# WiFi_module.net
KiCad netlist of a schematic drawn in EAGLE
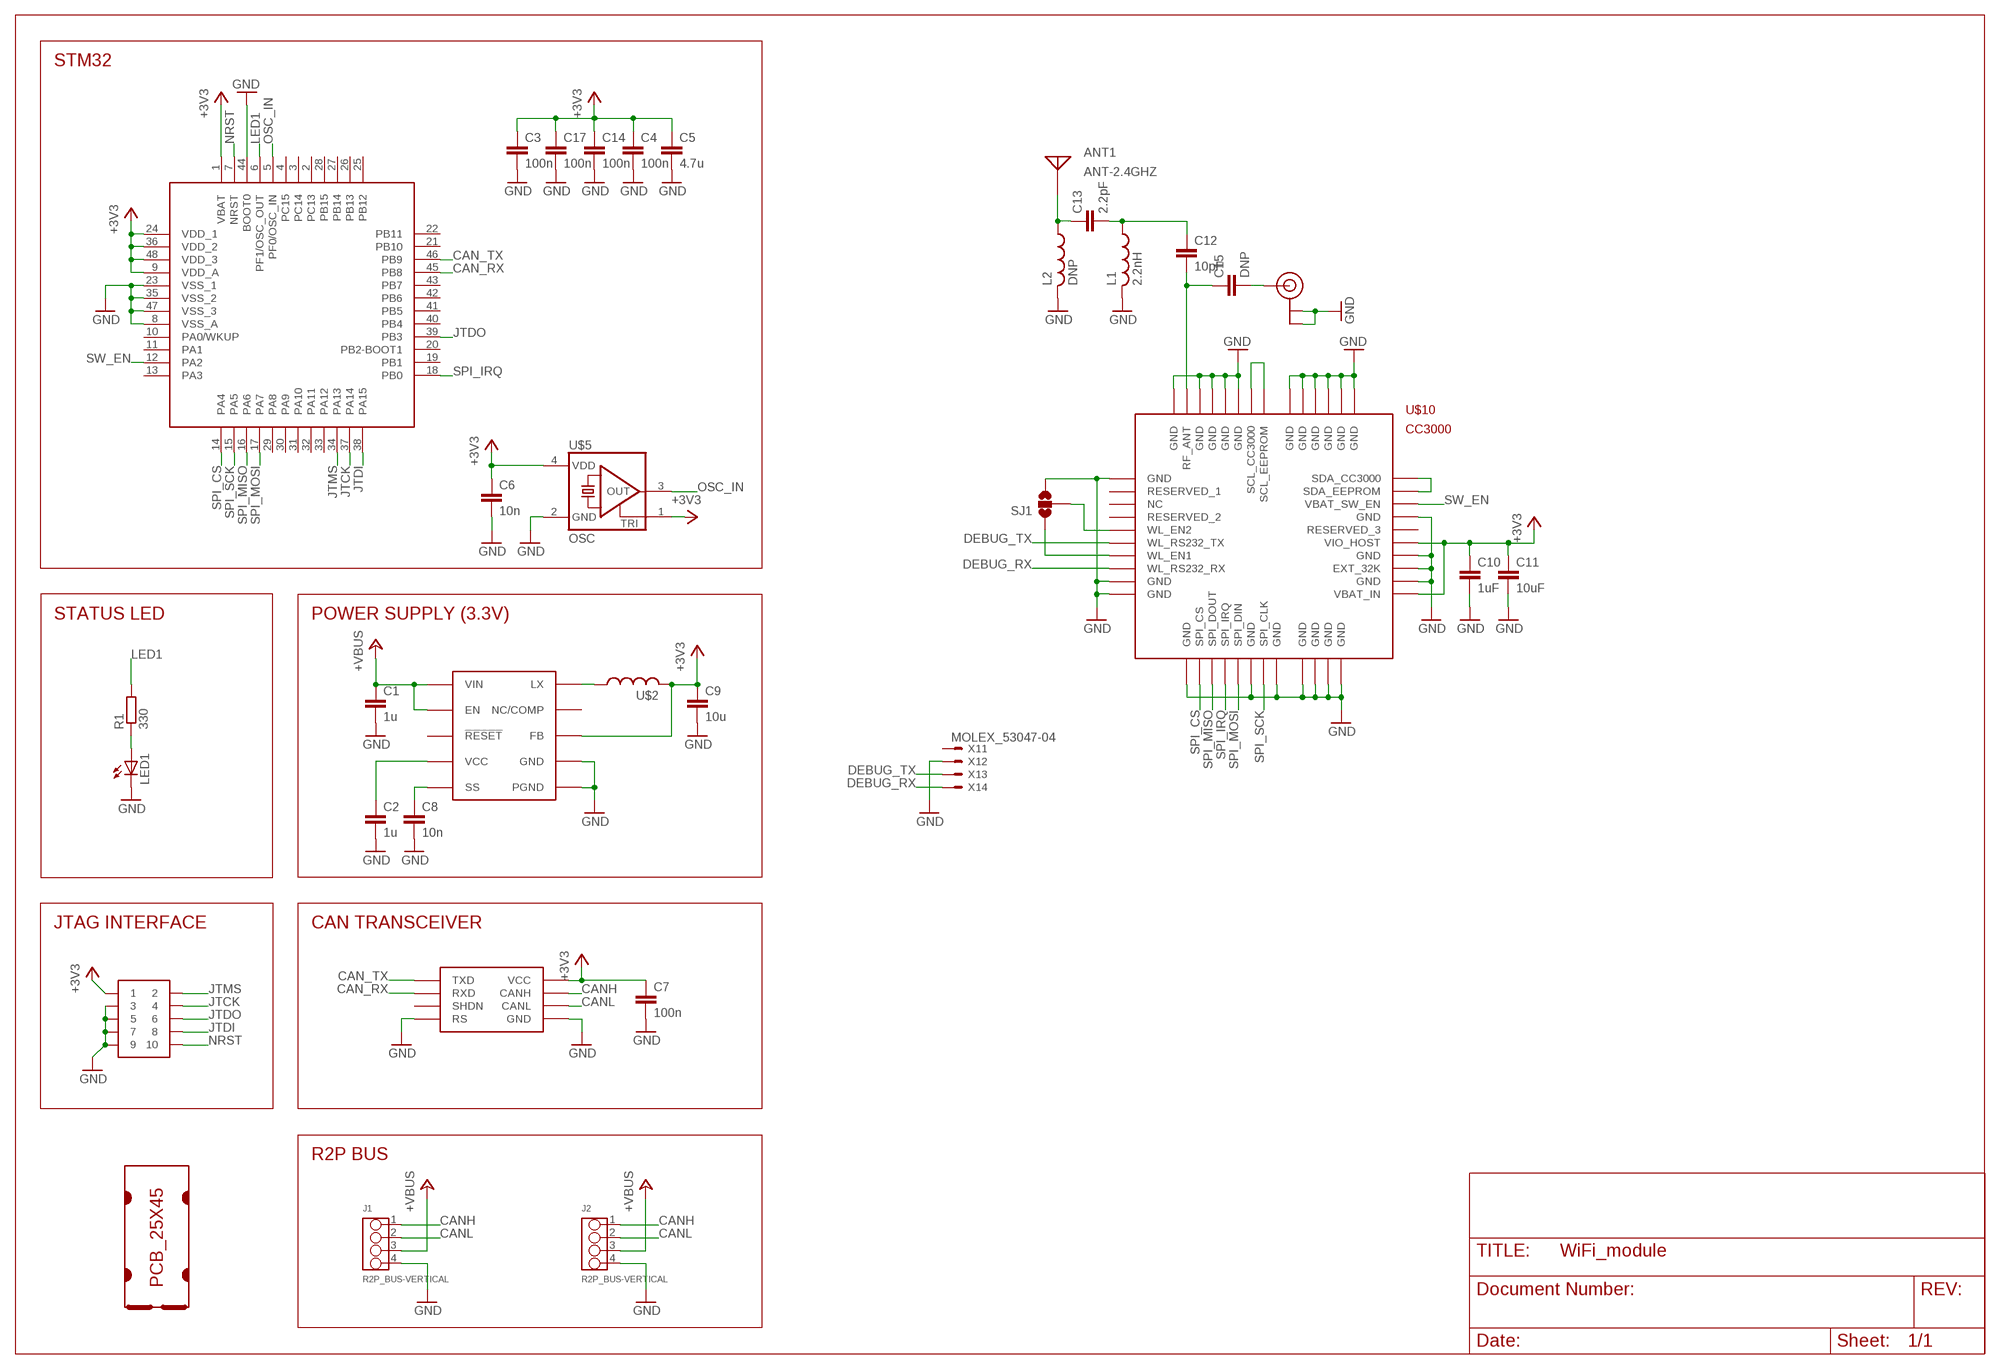
[diagram p0: schematic, sheet 1]

(export (version "E")
  (design (tool "Eeschema 10.0.6"))
  (components
    (comp (ref "ANT1")
      (value "ANT-2.4GHZ")
      (footprint "eagle-import:CHIP_ANTENNA_8X1")
      (libsource (lib "eagle-import") (part "ANT-2.4GHZ"))
    )
    (comp (ref "C1")
      (value "1u")
      (footprint "eagle-import:C1206")
      (libsource (lib "eagle-import") (part "C1206"))
    )
    (comp (ref "C2")
      (value "1u")
      (footprint "eagle-import:C0603")
      (libsource (lib "eagle-import") (part "C0603"))
    )
    (comp (ref "C3")
      (value "100n")
      (footprint "eagle-import:C0603")
      (libsource (lib "eagle-import") (part "C0603"))
    )
    (comp (ref "C4")
      (value "100n")
      (footprint "eagle-import:C0603")
      (libsource (lib "eagle-import") (part "C0603"))
    )
    (comp (ref "C5")
      (value "4.7u")
      (footprint "eagle-import:C0805")
      (libsource (lib "eagle-import") (part "C0805"))
    )
    (comp (ref "C6")
      (value "10n")
      (footprint "eagle-import:C0603")
      (libsource (lib "eagle-import") (part "C0603"))
    )
    (comp (ref "C7")
      (value "100n")
      (footprint "eagle-import:C0603")
      (libsource (lib "eagle-import") (part "C0603"))
    )
    (comp (ref "C8")
      (value "10n")
      (footprint "eagle-import:C0603")
      (libsource (lib "eagle-import") (part "C0603"))
    )
    (comp (ref "C9")
      (value "10u")
      (footprint "eagle-import:C0805")
      (libsource (lib "eagle-import") (part "C0805"))
    )
    (comp (ref "C10")
      (value "1uF")
      (footprint "eagle-import:C0603")
      (libsource (lib "eagle-import") (part "C0603"))
    )
    (comp (ref "C11")
      (value "10uF")
      (footprint "eagle-import:C0805")
      (libsource (lib "eagle-import") (part "C0805"))
    )
    (comp (ref "C12")
      (value "10pF")
      (footprint "eagle-import:C0402")
      (libsource (lib "eagle-import") (part "C0402"))
    )
    (comp (ref "C13")
      (value "2.2pF")
      (footprint "eagle-import:C0402")
      (libsource (lib "eagle-import") (part "C0402"))
    )
    (comp (ref "C14")
      (value "100n")
      (footprint "eagle-import:C0603")
      (libsource (lib "eagle-import") (part "C0603"))
    )
    (comp (ref "C15")
      (value "DNP")
      (footprint "eagle-import:C0402")
      (libsource (lib "eagle-import") (part "C0402"))
    )
    (comp (ref "C17")
      (value "100n")
      (footprint "eagle-import:C0603")
      (libsource (lib "eagle-import") (part "C0603"))
    )
    (comp (ref "J1")
      (value "R2P_BUS-VERTICAL")
      (footprint "eagle-import:OPL-EAGLE-LIBRARY_4P-2.0")
      (libsource (lib "eagle-import") (part "R2P_BUS-VERTICAL"))
    )
    (comp (ref "J2")
      (value "R2P_BUS-VERTICAL")
      (footprint "eagle-import:OPL-EAGLE-LIBRARY_4P-2.0")
      (libsource (lib "eagle-import") (part "R2P_BUS-VERTICAL"))
    )
    (comp (ref "L1")
      (value "2.2nH")
      (footprint "eagle-import:L0402")
      (libsource (lib "eagle-import") (part "L0402"))
    )
    (comp (ref "L2")
      (value "DNP")
      (footprint "eagle-import:L0402")
      (libsource (lib "eagle-import") (part "L0402"))
    )
    (comp (ref "LED1")
      (value "LED0805")
      (footprint "eagle-import:CHIPLED_0805")
      (libsource (lib "eagle-import") (part "LED0805"))
    )
    (comp (ref "R1")
      (value "330")
      (footprint "eagle-import:R0603")
      (libsource (lib "eagle-import") (part "R0603"))
    )
    (comp (ref "SJ1")
      (value "SOLDERJUMPER_2WAYPASTE1&2")
      (footprint "eagle-import:SJ_3_PASTE1&2")
      (libsource (lib "eagle-import") (part "SOLDERJUMPER_2WAYPASTE1&2"))
    )
    (comp (ref "SOT1")
      (value "MAX3051EKA")
      (footprint "eagle-import:SOT23-8L")
      (libsource (lib "eagle-import") (part "MAX3051EKA"))
    )
    (comp (ref "U$1")
      (value "PCB_25X45")
      (footprint "eagle-import:25X45")
      (libsource (lib "eagle-import") (part "PCB_25X45"))
    )
    (comp (ref "U$2")
      (value "LPS4018")
      (footprint "eagle-import:COILCRAFT_LPS4018")
      (libsource (lib "eagle-import") (part "LPS4018"))
    )
    (comp (ref "U$3")
      (value "MAX17501")
      (footprint "eagle-import:TDFN-10")
      (libsource (lib "eagle-import") (part "MAX17501"))
    )
    (comp (ref "U$4")
      (value "JTAG-TH")
      (footprint "eagle-import:SAMTEC_FTSH-105-TH")
      (libsource (lib "eagle-import") (part "JTAG-TH"))
    )
    (comp (ref "U$5")
      (value "OSC")
      (footprint "eagle-import:XTAL_2.5X2")
      (libsource (lib "eagle-import") (part "OSC"))
    )
    (comp (ref "U$6")
      (value "STM32F303CTX")
      (footprint "eagle-import:LQFP48")
      (libsource (lib "eagle-import") (part "STM32F303CTX"))
    )
    (comp (ref "U$10")
      (value "CC3000")
      (footprint "eagle-import:CC3000")
      (libsource (lib "eagle-import") (part "CC3000"))
    )
    (comp (ref "U$11")
      (value "U.FL")
      (footprint "eagle-import:U.FL")
      (libsource (lib "eagle-import") (part "U.FL"))
    )
    (comp (ref "X1")
      (value "MOLEX_53047-04")
      (footprint "eagle-import:MOLEX_53047-04")
      (fields (field (name "MF") "WALDOM/MOLEX") (field (name "MPN") "53047-0410"))
      (libsource (lib "eagle-import") (part "MOLEX_53?-04047"))
    )
  )
  (nets
    (net (code "1") (name "+3V3") (class "Default")
      (node (ref "C10") (pin "1") (pinfunction "1_1") (pintype "passive"))
      (node (ref "C11") (pin "1") (pinfunction "1_1") (pintype "passive"))
      (node (ref "C14") (pin "1") (pinfunction "1_1") (pintype "passive"))
      (node (ref "C17") (pin "1") (pinfunction "1_1") (pintype "passive"))
      (node (ref "C3") (pin "1") (pinfunction "1_1") (pintype "passive"))
      (node (ref "C4") (pin "1") (pinfunction "1_1") (pintype "passive"))
      (node (ref "C5") (pin "1") (pinfunction "1_1") (pintype "passive"))
      (node (ref "C6") (pin "1") (pinfunction "1_1") (pintype "passive"))
      (node (ref "C7") (pin "1") (pinfunction "1_1") (pintype "passive"))
      (node (ref "C9") (pin "1") (pinfunction "1_1") (pintype "passive"))
      (node (ref "SOT1") (pin "3") (pinfunction "VCC_3") (pintype "bidirectional"))
      (node (ref "U$10") (pin "P$19") (pinfunction "VBAT_IN_P$19") (pintype "bidirectional"))
      (node (ref "U$10") (pin "P$23") (pinfunction "VIO_HOST_P$23") (pintype "bidirectional"))
      (node (ref "U$2") (pin "P$2") (pinfunction "2_P$2") (pintype "passive"))
      (node (ref "U$3") (pin "P$5") (pinfunction "FB_P$5") (pintype "bidirectional"))
      (node (ref "U$4") (pin "1") (pinfunction "1_1") (pintype "bidirectional"))
      (node (ref "U$5") (pin "1") (pinfunction "TRI_1") (pintype "input"))
      (node (ref "U$5") (pin "4") (pinfunction "VDD_4") (pintype "power_in"))
      (node (ref "U$6") (pin "1") (pinfunction "VBAT_1") (pintype "bidirectional"))
      (node (ref "U$6") (pin "24") (pinfunction "VDD_1_24") (pintype "bidirectional"))
      (node (ref "U$6") (pin "36") (pinfunction "VDD_2_36") (pintype "bidirectional"))
      (node (ref "U$6") (pin "48") (pinfunction "VDD_3_48") (pintype "bidirectional"))
      (node (ref "U$6") (pin "9") (pinfunction "VDD_A_9") (pintype "bidirectional"))
    )
    (net (code "2") (name "+VBUS") (class "Default")
      (node (ref "C1") (pin "1") (pinfunction "1_1") (pintype "passive"))
      (node (ref "J1") (pin "3") (pinfunction "3_3") (pintype "bidirectional"))
      (node (ref "J2") (pin "3") (pinfunction "3_3") (pintype "bidirectional"))
      (node (ref "U$3") (pin "P$2") (pinfunction "VIN_P$2") (pintype "bidirectional"))
      (node (ref "U$3") (pin "P$3") (pinfunction "EN_P$3") (pintype "bidirectional"))
    )
    (net (code "3") (name "/CANH") (class "Default")
      (node (ref "J1") (pin "1") (pinfunction "1_1") (pintype "bidirectional"))
      (node (ref "J2") (pin "1") (pinfunction "1_1") (pintype "bidirectional"))
      (node (ref "SOT1") (pin "7") (pinfunction "CANH_7") (pintype "bidirectional"))
    )
    (net (code "4") (name "/CANL") (class "Default")
      (node (ref "J1") (pin "2") (pinfunction "2_2") (pintype "bidirectional"))
      (node (ref "J2") (pin "2") (pinfunction "2_2") (pintype "bidirectional"))
      (node (ref "SOT1") (pin "6") (pinfunction "CANL_6") (pintype "bidirectional"))
    )
    (net (code "5") (name "/CAN_RX") (class "Default")
      (node (ref "SOT1") (pin "4") (pinfunction "RXD_4") (pintype "bidirectional"))
      (node (ref "U$6") (pin "45") (pinfunction "PB8_45") (pintype "bidirectional"))
    )
    (net (code "6") (name "/CAN_TX") (class "Default")
      (node (ref "SOT1") (pin "1") (pinfunction "TXD_1") (pintype "bidirectional"))
      (node (ref "U$6") (pin "46") (pinfunction "PB9_46") (pintype "bidirectional"))
    )
    (net (code "7") (name "/DEBUG_RX") (class "Default")
      (node (ref "U$10") (pin "P$8") (pinfunction "WL_RS232_RX_P$8") (pintype "bidirectional"))
      (node (ref "X1") (pin "4") (pinfunction "S_4") (pintype "passive"))
    )
    (net (code "8") (name "/DEBUG_TX") (class "Default")
      (node (ref "U$10") (pin "P$6") (pinfunction "WL_RS232_TX_P$6") (pintype "bidirectional"))
      (node (ref "X1") (pin "3") (pinfunction "S_3") (pintype "passive"))
    )
    (net (code "9") (name "/JTCK") (class "Default")
      (node (ref "U$4") (pin "4") (pinfunction "4_4") (pintype "bidirectional"))
      (node (ref "U$6") (pin "37") (pinfunction "PA14_37") (pintype "bidirectional"))
    )
    (net (code "10") (name "/JTDI") (class "Default")
      (node (ref "U$4") (pin "8") (pinfunction "8_8") (pintype "bidirectional"))
      (node (ref "U$6") (pin "38") (pinfunction "PA15_38") (pintype "bidirectional"))
    )
    (net (code "11") (name "/JTDO") (class "Default")
      (node (ref "U$4") (pin "6") (pinfunction "6_6") (pintype "bidirectional"))
      (node (ref "U$6") (pin "39") (pinfunction "PB3_39") (pintype "bidirectional"))
    )
    (net (code "12") (name "/JTMS") (class "Default")
      (node (ref "U$4") (pin "2") (pinfunction "2_2") (pintype "bidirectional"))
      (node (ref "U$6") (pin "34") (pinfunction "PA13_34") (pintype "bidirectional"))
    )
    (net (code "13") (name "/LED1") (class "Default")
      (node (ref "R1") (pin "2") (pinfunction "2_2") (pintype "passive"))
      (node (ref "U$6") (pin "6") (pinfunction "PF1/OSC_OUT_6") (pintype "bidirectional"))
    )
    (net (code "14") (name "/NRST") (class "Default")
      (node (ref "U$4") (pin "10") (pinfunction "10_10") (pintype "bidirectional"))
      (node (ref "U$6") (pin "7") (pinfunction "NRST_7") (pintype "bidirectional"))
    )
    (net (code "15") (name "/OSC_IN") (class "Default")
      (node (ref "U$5") (pin "3") (pinfunction "OUT_3") (pintype "output"))
      (node (ref "U$6") (pin "5") (pinfunction "PF0/OSC_IN_5") (pintype "bidirectional"))
    )
    (net (code "16") (name "/SPI_CS") (class "Default")
      (node (ref "U$10") (pin "P$12") (pinfunction "SPI_CS_P$12") (pintype "bidirectional"))
      (node (ref "U$6") (pin "14") (pinfunction "PA4_14") (pintype "bidirectional"))
    )
    (net (code "17") (name "/SPI_IRQ") (class "Default")
      (node (ref "U$10") (pin "P$14") (pinfunction "SPI_IRQ_P$14") (pintype "bidirectional"))
      (node (ref "U$6") (pin "18") (pinfunction "PB0_18") (pintype "bidirectional"))
    )
    (net (code "18") (name "/SPI_MISO") (class "Default")
      (node (ref "U$10") (pin "P$13") (pinfunction "SPI_DOUT_P$13") (pintype "bidirectional"))
      (node (ref "U$6") (pin "16") (pinfunction "PA6_16") (pintype "bidirectional"))
    )
    (net (code "19") (name "/SPI_MOSI") (class "Default")
      (node (ref "U$10") (pin "P$15") (pinfunction "SPI_DIN_P$15") (pintype "bidirectional"))
      (node (ref "U$6") (pin "17") (pinfunction "PA7_17") (pintype "bidirectional"))
    )
    (net (code "20") (name "/SPI_SCK") (class "Default")
      (node (ref "U$10") (pin "P$17") (pinfunction "SPI_CLK_P$17") (pintype "bidirectional"))
      (node (ref "U$6") (pin "15") (pinfunction "PA5_15") (pintype "bidirectional"))
    )
    (net (code "21") (name "/SW_EN") (class "Default")
      (node (ref "U$10") (pin "P$26") (pinfunction "VBAT_SW_EN_P$26") (pintype "bidirectional"))
      (node (ref "U$6") (pin "12") (pinfunction "PA2_12") (pintype "bidirectional"))
    )
    (net (code "22") (name "GND") (class "Default")
      (node (ref "C1") (pin "2") (pinfunction "2_2") (pintype "passive"))
      (node (ref "C10") (pin "2") (pinfunction "2_2") (pintype "passive"))
      (node (ref "C11") (pin "2") (pinfunction "2_2") (pintype "passive"))
      (node (ref "C14") (pin "2") (pinfunction "2_2") (pintype "passive"))
      (node (ref "C17") (pin "2") (pinfunction "2_2") (pintype "passive"))
      (node (ref "C2") (pin "2") (pinfunction "2_2") (pintype "passive"))
      (node (ref "C3") (pin "2") (pinfunction "2_2") (pintype "passive"))
      (node (ref "C4") (pin "2") (pinfunction "2_2") (pintype "passive"))
      (node (ref "C5") (pin "2") (pinfunction "2_2") (pintype "passive"))
      (node (ref "C6") (pin "2") (pinfunction "2_2") (pintype "passive"))
      (node (ref "C7") (pin "2") (pinfunction "2_2") (pintype "passive"))
      (node (ref "C8") (pin "2") (pinfunction "2_2") (pintype "passive"))
      (node (ref "C9") (pin "2") (pinfunction "2_2") (pintype "passive"))
      (node (ref "J1") (pin "4") (pinfunction "4_4") (pintype "bidirectional"))
      (node (ref "J2") (pin "4") (pinfunction "4_4") (pintype "bidirectional"))
      (node (ref "L1") (pin "2") (pinfunction "2_2") (pintype "passive"))
      (node (ref "L2") (pin "2") (pinfunction "2_2") (pintype "passive"))
      (node (ref "LED1") (pin "C") (pinfunction "C_C") (pintype "passive"))
      (node (ref "SJ1") (pin "3") (pinfunction "3_3") (pintype "passive"))
      (node (ref "SOT1") (pin "2") (pinfunction "GND_2") (pintype "bidirectional"))
      (node (ref "SOT1") (pin "8") (pinfunction "RS_8") (pintype "bidirectional"))
      (node (ref "U$10") (pin "P$1") (pinfunction "GND_P$1") (pintype "bidirectional"))
      (node (ref "U$10") (pin "P$10") (pinfunction "GND_P$10") (pintype "bidirectional"))
      (node (ref "U$10") (pin "P$11") (pinfunction "GND_P$11") (pintype "bidirectional"))
      (node (ref "U$10") (pin "P$16") (pinfunction "GND_P$16") (pintype "bidirectional"))
      (node (ref "U$10") (pin "P$18") (pinfunction "GND_P$18") (pintype "bidirectional"))
      (node (ref "U$10") (pin "P$20") (pinfunction "GND_P$20") (pintype "bidirectional"))
      (node (ref "U$10") (pin "P$21") (pinfunction "EXT_32K_P$21") (pintype "bidirectional"))
      (node (ref "U$10") (pin "P$22") (pinfunction "GND_P$22") (pintype "bidirectional"))
      (node (ref "U$10") (pin "P$25") (pinfunction "GND_P$25") (pintype "bidirectional"))
      (node (ref "U$10") (pin "P$31") (pinfunction "GND_P$31") (pintype "bidirectional"))
      (node (ref "U$10") (pin "P$32") (pinfunction "GND_P$32") (pintype "bidirectional"))
      (node (ref "U$10") (pin "P$33") (pinfunction "GND_P$33") (pintype "bidirectional"))
      (node (ref "U$10") (pin "P$34") (pinfunction "GND_P$34") (pintype "bidirectional"))
      (node (ref "U$10") (pin "P$36") (pinfunction "GND_P$36") (pintype "bidirectional"))
      (node (ref "U$10") (pin "P$37") (pinfunction "GND_P$37") (pintype "bidirectional"))
      (node (ref "U$10") (pin "P$38") (pinfunction "GND_P$38") (pintype "bidirectional"))
      (node (ref "U$10") (pin "P$39") (pinfunction "GND_P$39") (pintype "bidirectional"))
      (node (ref "U$10") (pin "P$40") (pinfunction "GND_P$40") (pintype "bidirectional"))
      (node (ref "U$10") (pin "P$41") (pinfunction "GND_P$41") (pintype "bidirectional"))
      (node (ref "U$10") (pin "P$42") (pinfunction "GND_P$42") (pintype "bidirectional"))
      (node (ref "U$10") (pin "P$43") (pinfunction "GND_P$43") (pintype "bidirectional"))
      (node (ref "U$10") (pin "P$44") (pinfunction "GND_P$44") (pintype "bidirectional"))
      (node (ref "U$10") (pin "P$45") (pinfunction "GND_P$45") (pintype "bidirectional"))
      (node (ref "U$10") (pin "P$46") (pinfunction "GND_P$46") (pintype "bidirectional"))
      (node (ref "U$10") (pin "P$9") (pinfunction "GND_P$9") (pintype "bidirectional"))
      (node (ref "U$11") (pin "P$1") (pinfunction "GND_P$1") (pintype "bidirectional"))
      (node (ref "U$11") (pin "P$2") (pinfunction "GND_P$2") (pintype "bidirectional"))
      (node (ref "U$3") (pin "P$1") (pinfunction "PGND_P$1") (pintype "bidirectional"))
      (node (ref "U$3") (pin "P$11") (pinfunction "PGND_P$11") (pintype "bidirectional"))
      (node (ref "U$3") (pin "P$9") (pinfunction "GND_P$9") (pintype "bidirectional"))
      (node (ref "U$4") (pin "3") (pinfunction "3_3") (pintype "bidirectional"))
      (node (ref "U$4") (pin "5") (pinfunction "5_5") (pintype "bidirectional"))
      (node (ref "U$4") (pin "7") (pinfunction "7_7") (pintype "bidirectional"))
      (node (ref "U$4") (pin "9") (pinfunction "9_9") (pintype "bidirectional"))
      (node (ref "U$5") (pin "2") (pinfunction "GND_2") (pintype "power_in"))
      (node (ref "U$6") (pin "23") (pinfunction "VSS_1_23") (pintype "bidirectional"))
      (node (ref "U$6") (pin "35") (pinfunction "VSS_2_35") (pintype "bidirectional"))
      (node (ref "U$6") (pin "44") (pinfunction "BOOT0_44") (pintype "bidirectional"))
      (node (ref "U$6") (pin "47") (pinfunction "VSS_3_47") (pintype "bidirectional"))
      (node (ref "U$6") (pin "8") (pinfunction "VSS_A_8") (pintype "bidirectional"))
      (node (ref "X1") (pin "2") (pinfunction "S_2") (pintype "passive"))
    )
    (net (code "23") (name "Net-(ANT1-PadP$1)") (class "Default")
      (node (ref "ANT1") (pin "P$1") (pinfunction "P$1_P$1") (pintype "bidirectional"))
      (node (ref "C13") (pin "1") (pinfunction "1_1") (pintype "passive"))
      (node (ref "L2") (pin "1") (pinfunction "1_1") (pintype "passive"))
    )
    (net (code "24") (name "Net-(C12-Pad1)") (class "Default")
      (node (ref "C12") (pin "1") (pinfunction "1_1") (pintype "passive"))
      (node (ref "C13") (pin "2") (pinfunction "2_2") (pintype "passive"))
      (node (ref "L1") (pin "1") (pinfunction "1_1") (pintype "passive"))
    )
    (net (code "25") (name "Net-(LED1-PadA)") (class "Default")
      (node (ref "LED1") (pin "A") (pinfunction "A_A") (pintype "passive"))
      (node (ref "R1") (pin "1") (pinfunction "1_1") (pintype "passive"))
    )
    (net (code "26") (name "Net-(U$2-1)") (class "Default")
      (node (ref "U$2") (pin "P$1") (pinfunction "1_P$1") (pintype "passive"))
      (node (ref "U$3") (pin "P$10") (pinfunction "LX_P$10") (pintype "bidirectional"))
    )
    (net (code "27") (name "Net-(U$3-SS)") (class "Default")
      (node (ref "C8") (pin "1") (pinfunction "1_1") (pintype "passive"))
      (node (ref "U$3") (pin "P$6") (pinfunction "SS_P$6") (pintype "bidirectional"))
    )
    (net (code "28") (name "Net-(U$3-VCC)") (class "Default")
      (node (ref "C2") (pin "1") (pinfunction "1_1") (pintype "passive"))
      (node (ref "U$3") (pin "P$4") (pinfunction "VCC_P$4") (pintype "bidirectional"))
    )
    (net (code "29") (name "Net-(U$10-RF_ANT)") (class "Default")
      (node (ref "C12") (pin "2") (pinfunction "2_2") (pintype "passive"))
      (node (ref "C15") (pin "1") (pinfunction "1_1") (pintype "passive"))
      (node (ref "U$10") (pin "P$35") (pinfunction "RF_ANT_P$35") (pintype "bidirectional"))
    )
    (net (code "30") (name "Net-(U$10-SCL_CC3000)") (class "Default")
      (node (ref "U$10") (pin "P$29") (pinfunction "SCL_EEPROM_P$29") (pintype "bidirectional"))
      (node (ref "U$10") (pin "P$30") (pinfunction "SCL_CC3000_P$30") (pintype "bidirectional"))
    )
    (net (code "31") (name "Net-(U$10-SDA_CC3000)") (class "Default")
      (node (ref "U$10") (pin "P$27") (pinfunction "SDA_EEPROM_P$27") (pintype "bidirectional"))
      (node (ref "U$10") (pin "P$28") (pinfunction "SDA_CC3000_P$28") (pintype "bidirectional"))
    )
    (net (code "32") (name "Net-(U$10-WL_EN1)") (class "Default")
      (node (ref "SJ1") (pin "1") (pinfunction "1_1") (pintype "passive"))
      (node (ref "U$10") (pin "P$7") (pinfunction "WL_EN1_P$7") (pintype "bidirectional"))
    )
    (net (code "33") (name "Net-(U$10-WL_EN2)") (class "Default")
      (node (ref "SJ1") (pin "2") (pinfunction "2_2") (pintype "passive"))
      (node (ref "U$10") (pin "P$5") (pinfunction "WL_EN2_P$5") (pintype "bidirectional"))
    )
    (net (code "34") (name "Net-(U$11-SIGNAL)") (class "Default")
      (node (ref "C15") (pin "2") (pinfunction "2_2") (pintype "passive"))
      (node (ref "U$11") (pin "P$3") (pinfunction "SIGNAL_P$3") (pintype "bidirectional"))
    )
    (net (code "35") (name "unconnected-(SOT1-SHDN-Pad5)") (class "Default")
      (node (ref "SOT1") (pin "5") (pinfunction "SHDN_5") (pintype "bidirectional"))
    )
    (net (code "36") (name "unconnected-(U$3-NC{slash}COMP-PadP$7)") (class "Default")
      (node (ref "U$3") (pin "P$7") (pinfunction "NC/COMP_P$7") (pintype "bidirectional"))
    )
    (net (code "37") (name "unconnected-(U$3-~{RESET}-PadP$8)") (class "Default")
      (node (ref "U$3") (pin "P$8") (pinfunction "~{RESET}_P$8") (pintype "bidirectional"))
    )
    (net (code "38") (name "unconnected-(U$6-PA0{slash}WKUP-Pad10)") (class "Default")
      (node (ref "U$6") (pin "10") (pinfunction "PA0/WKUP_10") (pintype "bidirectional"))
    )
    (net (code "39") (name "unconnected-(U$6-PA1-Pad11)") (class "Default")
      (node (ref "U$6") (pin "11") (pinfunction "PA1_11") (pintype "bidirectional"))
    )
    (net (code "40") (name "unconnected-(U$6-PA3-Pad13)") (class "Default")
      (node (ref "U$6") (pin "13") (pinfunction "PA3_13") (pintype "bidirectional"))
    )
    (net (code "41") (name "unconnected-(U$6-PA8-Pad29)") (class "Default")
      (node (ref "U$6") (pin "29") (pinfunction "PA8_29") (pintype "bidirectional"))
    )
    (net (code "42") (name "unconnected-(U$6-PA9-Pad30)") (class "Default")
      (node (ref "U$6") (pin "30") (pinfunction "PA9_30") (pintype "bidirectional"))
    )
    (net (code "43") (name "unconnected-(U$6-PA10-Pad31)") (class "Default")
      (node (ref "U$6") (pin "31") (pinfunction "PA10_31") (pintype "bidirectional"))
    )
    (net (code "44") (name "unconnected-(U$6-PA11-Pad32)") (class "Default")
      (node (ref "U$6") (pin "32") (pinfunction "PA11_32") (pintype "bidirectional"))
    )
    (net (code "45") (name "unconnected-(U$6-PA12-Pad33)") (class "Default")
      (node (ref "U$6") (pin "33") (pinfunction "PA12_33") (pintype "bidirectional"))
    )
    (net (code "46") (name "unconnected-(U$6-PB1-Pad19)") (class "Default")
      (node (ref "U$6") (pin "19") (pinfunction "PB1_19") (pintype "bidirectional"))
    )
    (net (code "47") (name "unconnected-(U$6-PB2-BOOT1-Pad20)") (class "Default")
      (node (ref "U$6") (pin "20") (pinfunction "PB2-BOOT1_20") (pintype "bidirectional"))
    )
    (net (code "48") (name "unconnected-(U$6-PB4-Pad40)") (class "Default")
      (node (ref "U$6") (pin "40") (pinfunction "PB4_40") (pintype "bidirectional"))
    )
    (net (code "49") (name "unconnected-(U$6-PB5-Pad41)") (class "Default")
      (node (ref "U$6") (pin "41") (pinfunction "PB5_41") (pintype "bidirectional"))
    )
    (net (code "50") (name "unconnected-(U$6-PB6-Pad42)") (class "Default")
      (node (ref "U$6") (pin "42") (pinfunction "PB6_42") (pintype "bidirectional"))
    )
    (net (code "51") (name "unconnected-(U$6-PB7-Pad43)") (class "Default")
      (node (ref "U$6") (pin "43") (pinfunction "PB7_43") (pintype "bidirectional"))
    )
    (net (code "52") (name "unconnected-(U$6-PB10-Pad21)") (class "Default")
      (node (ref "U$6") (pin "21") (pinfunction "PB10_21") (pintype "bidirectional"))
    )
    (net (code "53") (name "unconnected-(U$6-PB11-Pad22)") (class "Default")
      (node (ref "U$6") (pin "22") (pinfunction "PB11_22") (pintype "bidirectional"))
    )
    (net (code "54") (name "unconnected-(U$6-PB12-Pad25)") (class "Default")
      (node (ref "U$6") (pin "25") (pinfunction "PB12_25") (pintype "bidirectional"))
    )
    (net (code "55") (name "unconnected-(U$6-PB13-Pad26)") (class "Default")
      (node (ref "U$6") (pin "26") (pinfunction "PB13_26") (pintype "bidirectional"))
    )
    (net (code "56") (name "unconnected-(U$6-PB14-Pad27)") (class "Default")
      (node (ref "U$6") (pin "27") (pinfunction "PB14_27") (pintype "bidirectional"))
    )
    (net (code "57") (name "unconnected-(U$6-PB15-Pad28)") (class "Default")
      (node (ref "U$6") (pin "28") (pinfunction "PB15_28") (pintype "bidirectional"))
    )
    (net (code "58") (name "unconnected-(U$6-PC13-Pad2)") (class "Default")
      (node (ref "U$6") (pin "2") (pinfunction "PC13_2") (pintype "bidirectional"))
    )
    (net (code "59") (name "unconnected-(U$6-PC14-Pad3)") (class "Default")
      (node (ref "U$6") (pin "3") (pinfunction "PC14_3") (pintype "bidirectional"))
    )
    (net (code "60") (name "unconnected-(U$6-PC15-Pad4)") (class "Default")
      (node (ref "U$6") (pin "4") (pinfunction "PC15_4") (pintype "bidirectional"))
    )
    (net (code "61") (name "unconnected-(U$10-NC-PadP$3)") (class "Default")
      (node (ref "U$10") (pin "P$3") (pinfunction "NC_P$3") (pintype "bidirectional"))
    )
    (net (code "62") (name "unconnected-(U$10-RESERVED_1-PadP$2)") (class "Default")
      (node (ref "U$10") (pin "P$2") (pinfunction "RESERVED_1_P$2") (pintype "bidirectional"))
    )
    (net (code "63") (name "unconnected-(U$10-RESERVED_2-PadP$4)") (class "Default")
      (node (ref "U$10") (pin "P$4") (pinfunction "RESERVED_2_P$4") (pintype "bidirectional"))
    )
    (net (code "64") (name "unconnected-(U$10-RESERVED_3-PadP$24)") (class "Default")
      (node (ref "U$10") (pin "P$24") (pinfunction "RESERVED_3_P$24") (pintype "bidirectional"))
    )
    (net (code "65") (name "unconnected-(X1A-S-Pad1)") (class "Default")
      (node (ref "X1") (pin "1") (pinfunction "S_1") (pintype "passive"))
    )
  )
)
